# LaptopCharger.net
KiCad netlist of a schematic drawn in Altium Designer
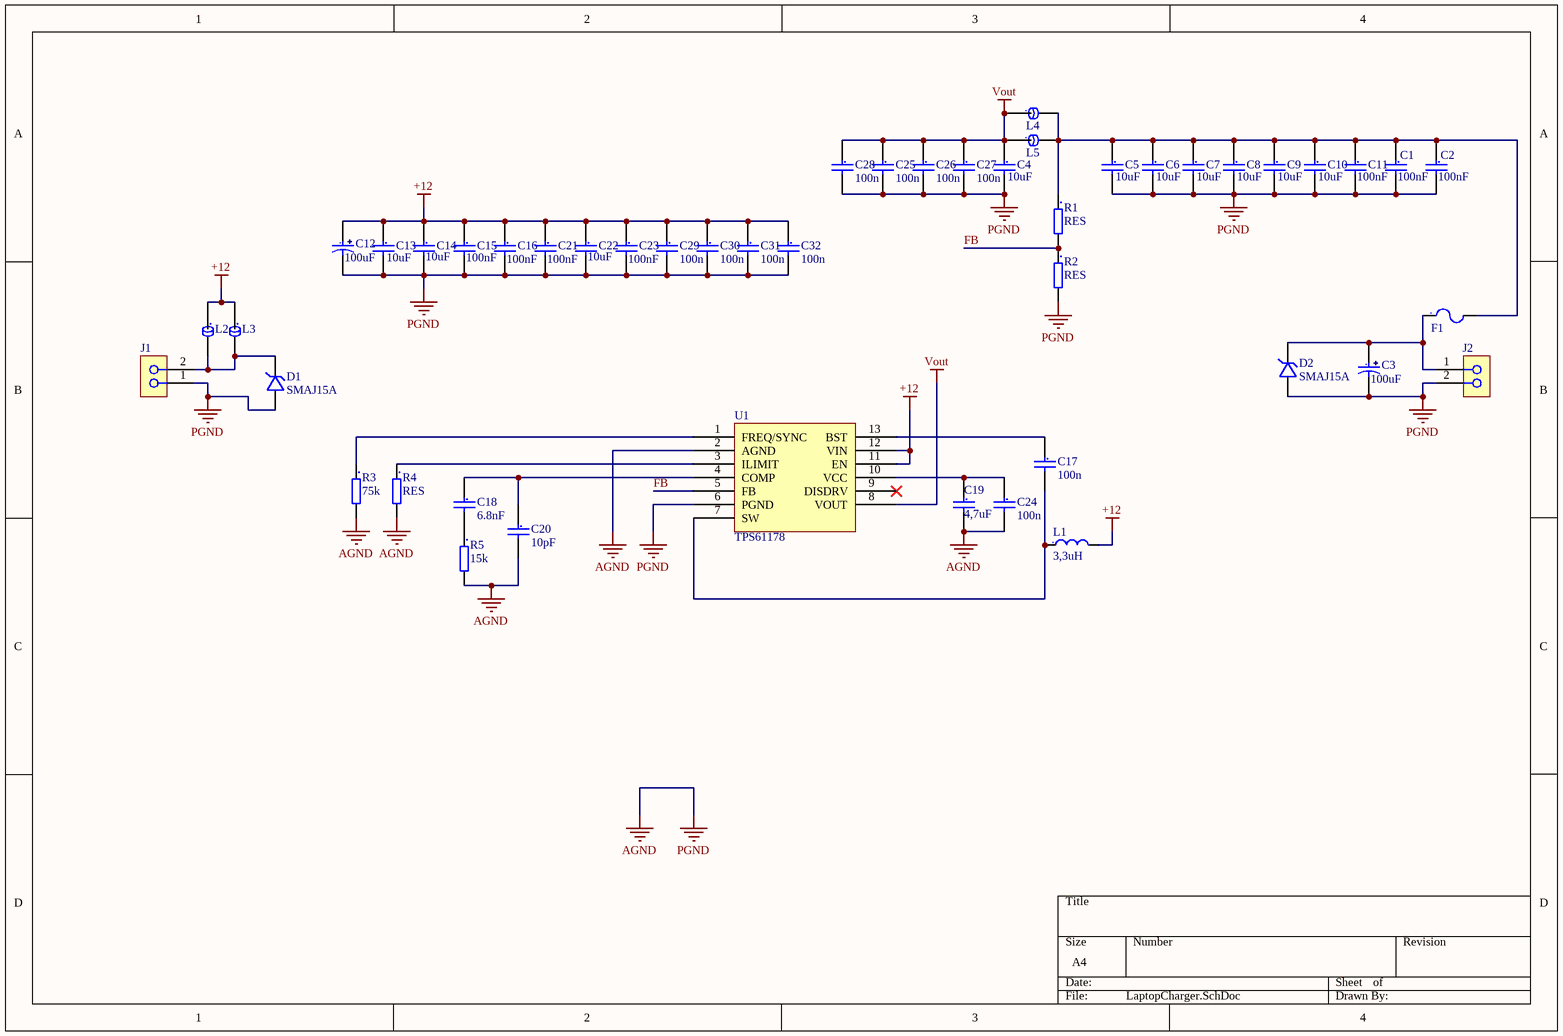
[diagram p0: LaptopCharger.SchDoc]

(export (version "E")
  (design (tool "Eeschema 10.0.6"))
  (components
    (comp (ref "C1") (value "100nF") (footprint "C0603_N") (libsource (lib "MyLib") (part "CAP")))
    (comp (ref "C2") (value "100nF") (footprint "C0603_N") (libsource (lib "MyLib") (part "CAP")))
    (comp (ref "C3") (value "100uF") (footprint "CPE_6.6x6.6x5.4") (libsource (lib "MyLib") (part "CAP_POL")))
    (comp (ref "C4") (value "10uF") (footprint "C0805_N") (libsource (lib "MyLib") (part "CAP")))
    (comp (ref "C5") (value "10uF") (footprint "C0805_N") (libsource (lib "MyLib") (part "CAP")))
    (comp (ref "C6") (value "10uF") (footprint "C0805_N") (libsource (lib "MyLib") (part "CAP")))
    (comp (ref "C7") (value "10uF") (footprint "C0805_N") (libsource (lib "MyLib") (part "CAP")))
    (comp (ref "C8") (value "10uF") (footprint "C0805_N") (libsource (lib "MyLib") (part "CAP")))
    (comp (ref "C9") (value "10uF") (footprint "C0805_N") (libsource (lib "MyLib") (part "CAP")))
    (comp (ref "C10") (value "10uF") (footprint "C0805_N") (libsource (lib "MyLib") (part "CAP")))
    (comp (ref "C11") (value "100nF") (footprint "C0603_N") (libsource (lib "MyLib") (part "CAP")))
    (comp (ref "C12")
      (value "100uF")
      (footprint "CPE_6.6x6.6x5.4")
      (libsource (lib "MyLib") (part "CAP_POL"))
    )
    (comp (ref "C13") (value "10uF") (footprint "C0805_N") (libsource (lib "MyLib") (part "CAP")))
    (comp (ref "C14") (value "10uF") (footprint "C0805_N") (libsource (lib "MyLib") (part "CAP")))
    (comp (ref "C15") (value "100nF") (footprint "C0603_N") (libsource (lib "MyLib") (part "CAP")))
    (comp (ref "C16") (value "100nF") (footprint "C0603_N") (libsource (lib "MyLib") (part "CAP")))
    (comp (ref "C17") (value "100n") (footprint "C0402_N") (libsource (lib "MyLib") (part "CAP")))
    (comp (ref "C18") (value "6.8nF") (footprint "C0603_N") (libsource (lib "MyLib") (part "CAP")))
    (comp (ref "C19") (value "4,7uF") (footprint "C0603_N") (libsource (lib "MyLib") (part "CAP")))
    (comp (ref "C20") (value "10pF") (footprint "C0603_N") (libsource (lib "MyLib") (part "CAP")))
    (comp (ref "C21") (value "100nF") (footprint "C0603_N") (libsource (lib "MyLib") (part "CAP")))
    (comp (ref "C22") (value "10uF") (footprint "C0805_N") (libsource (lib "MyLib") (part "CAP")))
    (comp (ref "C23") (value "100nF") (footprint "C0603_N") (libsource (lib "MyLib") (part "CAP")))
    (comp (ref "C24") (value "100n") (footprint "C0402_N") (libsource (lib "MyLib") (part "CAP")))
    (comp (ref "C25") (value "100n") (footprint "C0402_N") (libsource (lib "MyLib") (part "CAP")))
    (comp (ref "C26") (value "100n") (footprint "C0402_N") (libsource (lib "MyLib") (part "CAP")))
    (comp (ref "C27") (value "100n") (footprint "C0402_N") (libsource (lib "MyLib") (part "CAP")))
    (comp (ref "C28") (value "100n") (footprint "C0402_N") (libsource (lib "MyLib") (part "CAP")))
    (comp (ref "C29") (value "100n") (footprint "C0402_N") (libsource (lib "MyLib") (part "CAP")))
    (comp (ref "C30") (value "100n") (footprint "C0402_N") (libsource (lib "MyLib") (part "CAP")))
    (comp (ref "C31") (value "100n") (footprint "C0402_N") (libsource (lib "MyLib") (part "CAP")))
    (comp (ref "C32") (value "100n") (footprint "C0402_N") (libsource (lib "MyLib") (part "CAP")))
    (comp (ref "D1") (value "SMAJ15A") (footprint "DO-214AC") (libsource (lib "MyLib") (part "DIODE_ZENER")))
    (comp (ref "D2") (value "SMAJ15A") (footprint "DO-214AC") (libsource (lib "MyLib") (part "DIODE_ZENER")))
    (comp (ref "F1") (value "FUSE") (footprint "FUSE1210") (libsource (lib "MyLib") (part "FUSE")))
    (comp (ref "J1")
      (value "~")
      (footprint "CABLE_ENTRY_SCREWLESS_2_45_381")
      (description "Socket")
      (libsource (lib "") (part "SOCHDR_2X1_1"))
    )
    (comp (ref "J2")
      (value "~")
      (footprint "CABLE_ENTRY_SCREWLESS_2_45_381")
      (description "Socket")
      (libsource (lib "MyLib") (part "SOCHDR_2X1"))
    )
    (comp (ref "L1")
      (value "3,3uH")
      (footprint "IND_IDCS-7328")
      (description "Inductor")
      (libsource (lib "MyLib") (part "IND"))
    )
    (comp (ref "L2") (value "~") (footprint "BEAD_0805_N") (libsource (lib "") (part "BEAD_1")))
    (comp (ref "L3") (value "~") (footprint "BEAD_0805_N") (libsource (lib "") (part "BEAD_1")))
    (comp (ref "L4") (value "~") (footprint "BEAD_0805_N") (libsource (lib "MyLib") (part "BEAD")))
    (comp (ref "L5") (value "~") (footprint "BEAD_0805_N") (libsource (lib "MyLib") (part "BEAD")))
    (comp (ref "R1") (value "RES") (footprint "R0603_N") (libsource (lib "MyLib") (part "RES")))
    (comp (ref "R2") (value "RES") (footprint "R0603_N") (libsource (lib "MyLib") (part "RES")))
    (comp (ref "R3") (value "75k") (footprint "R0402_N") (libsource (lib "MyLib") (part "RES")))
    (comp (ref "R4") (value "RES") (footprint "R0402_N") (libsource (lib "MyLib") (part "RES")))
    (comp (ref "R5") (value "15k") (footprint "R0603_N") (libsource (lib "MyLib") (part "RES")))
    (comp (ref "U1")
      (value "TPS61178")
      (footprint "VQFN-HR-13")
      (description "TPS61178x 20-V, 10-A Fully-Integrated Synchronous Boost with Load Disconnect Control")
      (libsource (lib "MyLib") (part "TPS61178"))
    )
  )
  (nets
    (net (code "1") (name "+12") (class "Default")
      (node (ref "C12") (pin "P") (pinfunction "P_P") (pintype "passive"))
      (node (ref "C13") (pin "1") (pinfunction "1_1") (pintype "passive"))
      (node (ref "C14") (pin "1") (pinfunction "1_1") (pintype "passive"))
      (node (ref "C15") (pin "1") (pinfunction "1_1") (pintype "passive"))
      (node (ref "C16") (pin "1") (pinfunction "1_1") (pintype "passive"))
      (node (ref "C21") (pin "1") (pinfunction "1_1") (pintype "passive"))
      (node (ref "C22") (pin "1") (pinfunction "1_1") (pintype "passive"))
      (node (ref "C23") (pin "1") (pinfunction "1_1") (pintype "passive"))
      (node (ref "C29") (pin "1") (pinfunction "1_1") (pintype "passive"))
      (node (ref "C30") (pin "1") (pinfunction "1_1") (pintype "passive"))
      (node (ref "C31") (pin "1") (pinfunction "1_1") (pintype "passive"))
      (node (ref "C32") (pin "1") (pinfunction "1_1") (pintype "passive"))
      (node (ref "L1") (pin "2") (pinfunction "2_2") (pintype "passive"))
      (node (ref "L2") (pin "1") (pinfunction "1_1") (pintype "passive"))
      (node (ref "L3") (pin "1") (pinfunction "1_1") (pintype "passive"))
      (node (ref "U1") (pin "11") (pinfunction "EN_11") (pintype "passive"))
      (node (ref "U1") (pin "12") (pinfunction "VIN_12") (pintype "passive"))
    )
    (net (code "2") (name "/FB") (class "Default")
      (node (ref "R1") (pin "2") (pinfunction "2_2") (pintype "passive"))
      (node (ref "R2") (pin "1") (pinfunction "1_1") (pintype "passive"))
      (node (ref "U1") (pin "5") (pinfunction "FB_5") (pintype "passive"))
    )
    (net (code "3") (name "AGND") (class "Default")
      (node (ref "C1") (pin "2") (pinfunction "2_2") (pintype "passive"))
      (node (ref "C10") (pin "2") (pinfunction "2_2") (pintype "passive"))
      (node (ref "C11") (pin "2") (pinfunction "2_2") (pintype "passive"))
      (node (ref "C12") (pin "N") (pinfunction "N_N") (pintype "passive"))
      (node (ref "C13") (pin "2") (pinfunction "2_2") (pintype "passive"))
      (node (ref "C14") (pin "2") (pinfunction "2_2") (pintype "passive"))
      (node (ref "C15") (pin "2") (pinfunction "2_2") (pintype "passive"))
      (node (ref "C16") (pin "2") (pinfunction "2_2") (pintype "passive"))
      (node (ref "C19") (pin "2") (pinfunction "2_2") (pintype "passive"))
      (node (ref "C2") (pin "2") (pinfunction "2_2") (pintype "passive"))
      (node (ref "C20") (pin "2") (pinfunction "2_2") (pintype "passive"))
      (node (ref "C21") (pin "2") (pinfunction "2_2") (pintype "passive"))
      (node (ref "C22") (pin "2") (pinfunction "2_2") (pintype "passive"))
      (node (ref "C23") (pin "2") (pinfunction "2_2") (pintype "passive"))
      (node (ref "C24") (pin "2") (pinfunction "2_2") (pintype "passive"))
      (node (ref "C25") (pin "2") (pinfunction "2_2") (pintype "passive"))
      (node (ref "C26") (pin "2") (pinfunction "2_2") (pintype "passive"))
      (node (ref "C27") (pin "2") (pinfunction "2_2") (pintype "passive"))
      (node (ref "C28") (pin "2") (pinfunction "2_2") (pintype "passive"))
      (node (ref "C29") (pin "2") (pinfunction "2_2") (pintype "passive"))
      (node (ref "C3") (pin "N") (pinfunction "N_N") (pintype "passive"))
      (node (ref "C30") (pin "2") (pinfunction "2_2") (pintype "passive"))
      (node (ref "C31") (pin "2") (pinfunction "2_2") (pintype "passive"))
      (node (ref "C32") (pin "2") (pinfunction "2_2") (pintype "passive"))
      (node (ref "C4") (pin "2") (pinfunction "2_2") (pintype "passive"))
      (node (ref "C5") (pin "2") (pinfunction "2_2") (pintype "passive"))
      (node (ref "C6") (pin "2") (pinfunction "2_2") (pintype "passive"))
      (node (ref "C7") (pin "2") (pinfunction "2_2") (pintype "passive"))
      (node (ref "C8") (pin "2") (pinfunction "2_2") (pintype "passive"))
      (node (ref "C9") (pin "2") (pinfunction "2_2") (pintype "passive"))
      (node (ref "D1") (pin "A") (pinfunction "A_A") (pintype "passive"))
      (node (ref "D2") (pin "A") (pinfunction "A_A") (pintype "passive"))
      (node (ref "J1") (pin "1") (pinfunction "1_1") (pintype "passive"))
      (node (ref "J2") (pin "2") (pinfunction "2_2") (pintype "passive"))
      (node (ref "R2") (pin "2") (pinfunction "2_2") (pintype "passive"))
      (node (ref "R3") (pin "2") (pinfunction "2_2") (pintype "passive"))
      (node (ref "R4") (pin "2") (pinfunction "2_2") (pintype "passive"))
      (node (ref "R5") (pin "2") (pinfunction "2_2") (pintype "passive"))
      (node (ref "U1") (pin "2") (pinfunction "AGND_2") (pintype "passive"))
      (node (ref "U1") (pin "6") (pinfunction "PGND_6") (pintype "passive"))
    )
    (net (code "4") (name "Net-(C1-Pad1)") (class "Default")
      (node (ref "C1") (pin "1") (pinfunction "1_1") (pintype "passive"))
      (node (ref "C10") (pin "1") (pinfunction "1_1") (pintype "passive"))
      (node (ref "C11") (pin "1") (pinfunction "1_1") (pintype "passive"))
      (node (ref "C2") (pin "1") (pinfunction "1_1") (pintype "passive"))
      (node (ref "C5") (pin "1") (pinfunction "1_1") (pintype "passive"))
      (node (ref "C6") (pin "1") (pinfunction "1_1") (pintype "passive"))
      (node (ref "C7") (pin "1") (pinfunction "1_1") (pintype "passive"))
      (node (ref "C8") (pin "1") (pinfunction "1_1") (pintype "passive"))
      (node (ref "C9") (pin "1") (pinfunction "1_1") (pintype "passive"))
      (node (ref "F1") (pin "2") (pinfunction "2_2") (pintype "passive"))
      (node (ref "L4") (pin "2") (pinfunction "2_2") (pintype "passive"))
      (node (ref "L5") (pin "2") (pinfunction "2_2") (pintype "passive"))
      (node (ref "R1") (pin "1") (pinfunction "1_1") (pintype "passive"))
    )
    (net (code "5") (name "Net-(C3-PadP)") (class "Default")
      (node (ref "C3") (pin "P") (pinfunction "P_P") (pintype "passive"))
      (node (ref "D2") (pin "C") (pinfunction "C_C") (pintype "passive"))
      (node (ref "F1") (pin "1") (pinfunction "1_1") (pintype "passive"))
      (node (ref "J2") (pin "1") (pinfunction "1_1") (pintype "passive"))
    )
    (net (code "6") (name "Net-(C18-Pad2)") (class "Default")
      (node (ref "C18") (pin "2") (pinfunction "2_2") (pintype "passive"))
      (node (ref "R5") (pin "1") (pinfunction "1_1") (pintype "passive"))
    )
    (net (code "7") (name "Net-(D1-PadC)") (class "Default")
      (node (ref "D1") (pin "C") (pinfunction "C_C") (pintype "passive"))
      (node (ref "J1") (pin "2") (pinfunction "2_2") (pintype "passive"))
      (node (ref "L2") (pin "2") (pinfunction "2_2") (pintype "passive"))
      (node (ref "L3") (pin "2") (pinfunction "2_2") (pintype "passive"))
    )
    (net (code "8") (name "Net-(U1-BST)") (class "Default")
      (node (ref "C17") (pin "1") (pinfunction "1_1") (pintype "passive"))
      (node (ref "U1") (pin "13") (pinfunction "BST_13") (pintype "passive"))
    )
    (net (code "9") (name "Net-(U1-COMP)") (class "Default")
      (node (ref "C18") (pin "1") (pinfunction "1_1") (pintype "passive"))
      (node (ref "C20") (pin "1") (pinfunction "1_1") (pintype "passive"))
      (node (ref "U1") (pin "4") (pinfunction "COMP_4") (pintype "passive"))
    )
    (net (code "10") (name "Net-(U1-FREQ{slash}SYNC)") (class "Default")
      (node (ref "R3") (pin "1") (pinfunction "1_1") (pintype "passive"))
      (node (ref "U1") (pin "1") (pinfunction "FREQ/SYNC_1") (pintype "passive"))
    )
    (net (code "11") (name "Net-(U1-ILIMIT)") (class "Default")
      (node (ref "R4") (pin "1") (pinfunction "1_1") (pintype "passive"))
      (node (ref "U1") (pin "3") (pinfunction "ILIMIT_3") (pintype "passive"))
    )
    (net (code "12") (name "Net-(U1-SW)") (class "Default")
      (node (ref "C17") (pin "2") (pinfunction "2_2") (pintype "passive"))
      (node (ref "L1") (pin "1") (pinfunction "1_1") (pintype "passive"))
      (node (ref "U1") (pin "7") (pinfunction "SW_7") (pintype "passive"))
    )
    (net (code "13") (name "Net-(U1-VCC)") (class "Default")
      (node (ref "C19") (pin "1") (pinfunction "1_1") (pintype "passive"))
      (node (ref "C24") (pin "1") (pinfunction "1_1") (pintype "passive"))
      (node (ref "U1") (pin "10") (pinfunction "VCC_10") (pintype "passive"))
    )
    (net (code "14") (name "Vout") (class "Default")
      (node (ref "C25") (pin "1") (pinfunction "1_1") (pintype "passive"))
      (node (ref "C26") (pin "1") (pinfunction "1_1") (pintype "passive"))
      (node (ref "C27") (pin "1") (pinfunction "1_1") (pintype "passive"))
      (node (ref "C28") (pin "1") (pinfunction "1_1") (pintype "passive"))
      (node (ref "C4") (pin "1") (pinfunction "1_1") (pintype "passive"))
      (node (ref "L4") (pin "1") (pinfunction "1_1") (pintype "passive"))
      (node (ref "L5") (pin "1") (pinfunction "1_1") (pintype "passive"))
      (node (ref "U1") (pin "8") (pinfunction "VOUT_8") (pintype "passive"))
    )
    (net (code "15") (name "unconnected-(U1-DISDRV-Pad9)") (class "Default")
      (node (ref "U1") (pin "9") (pinfunction "DISDRV_9") (pintype "passive+no_connect"))
    )
  )
)
